# esc_connector.net
KiCad netlist of a schematic drawn in Altium Designer
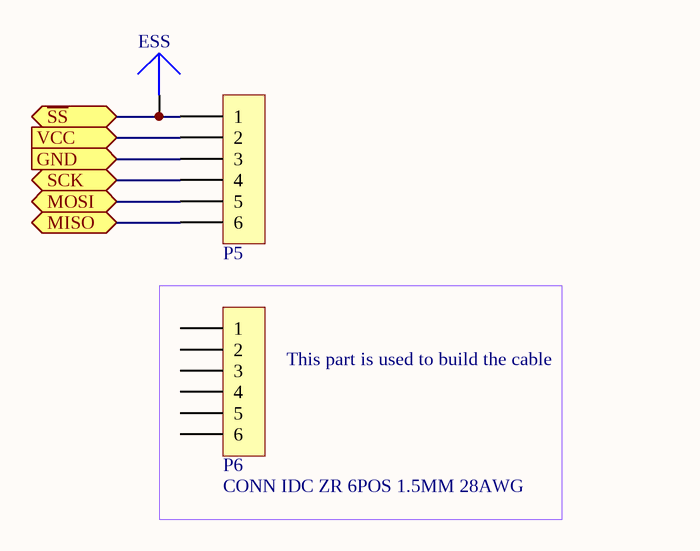
[diagram p0: esc_connector.SchDoc]

(export (version "E")
  (design (tool "Eeschema 10.0.6"))
  (components
    (comp (ref "ESS")
      (value "TESTPOINT-ARROW-BLUE")
      (footprint "G-PIN_1mm-CIRCLE")
      (description "Tespoint")
      (libsource (lib "Connector#csv") (part "TESTP_SIG_1mm"))
    )
    (comp (ref "P5")
      (value "HEADER-6x1")
      (footprint "X-JST-S6B-ZR")
      (description "CONN HEADER ZH SIDE 6POS 1.5MM")
      (fields
        (field (name "MANUFACTURER") "JST Sales America Inc")
        (field (name "MANUFACTURER PART NUMBER") "S6B-ZR(LF)(SN)")
      )
      (libsource (lib "Connector#csv") (part "HEADER_6x1_1.5mm_ZH_TH"))
    )
    (comp (ref "P6")
      (value "HEADER-6x1_Mech")
      (description "CONN IDC ZR 6POS 1.5MM 28AWG")
      (fields
        (field (name "MANUFACTURER") "JST Sales America Inc")
        (field (name "MANUFACTURER PART NUMBER") "06ZR-8M-P")
      )
      (libsource (lib "Connector#csv") (part "HEADER_6x1_1.5mm_ZH_TH_Wire"))
    )
  )
  (nets
    (net (code "1") (name "/GND") (class "Default")
      (node (ref "P5") (pin "3") (pinfunction "3_3") (pintype "passive"))
    )
    (net (code "2") (name "/MISO") (class "Default")
      (node (ref "P5") (pin "6") (pinfunction "6_6") (pintype "passive"))
    )
    (net (code "3") (name "/MOSI") (class "Default")
      (node (ref "P5") (pin "5") (pinfunction "5_5") (pintype "passive"))
    )
    (net (code "4") (name "/SCK") (class "Default")
      (node (ref "P5") (pin "4") (pinfunction "4_4") (pintype "passive"))
    )
    (net (code "5") (name "/VCC") (class "Default")
      (node (ref "P5") (pin "2") (pinfunction "2_2") (pintype "passive"))
    )
    (net (code "6") (name "/~{SS}") (class "Default")
      (node (ref "ESS") (pin "1") (pinfunction "1_1") (pintype "passive"))
      (node (ref "P5") (pin "1") (pinfunction "1_1") (pintype "passive"))
    )
    (net (code "7") (name "unconnected-(P6-Pad1)") (class "Default")
      (node (ref "P6") (pin "1") (pinfunction "1_1") (pintype "passive"))
    )
    (net (code "8") (name "unconnected-(P6-Pad2)") (class "Default")
      (node (ref "P6") (pin "2") (pinfunction "2_2") (pintype "passive"))
    )
    (net (code "9") (name "unconnected-(P6-Pad3)") (class "Default")
      (node (ref "P6") (pin "3") (pinfunction "3_3") (pintype "passive"))
    )
    (net (code "10") (name "unconnected-(P6-Pad4)") (class "Default")
      (node (ref "P6") (pin "4") (pinfunction "4_4") (pintype "passive"))
    )
    (net (code "11") (name "unconnected-(P6-Pad5)") (class "Default")
      (node (ref "P6") (pin "5") (pinfunction "5_5") (pintype "passive"))
    )
    (net (code "12") (name "unconnected-(P6-Pad6)") (class "Default")
      (node (ref "P6") (pin "6") (pinfunction "6_6") (pintype "passive"))
    )
  )
)
